# FPGA_Bank0-2.net
KiCad netlist of a schematic drawn in Altium Designer
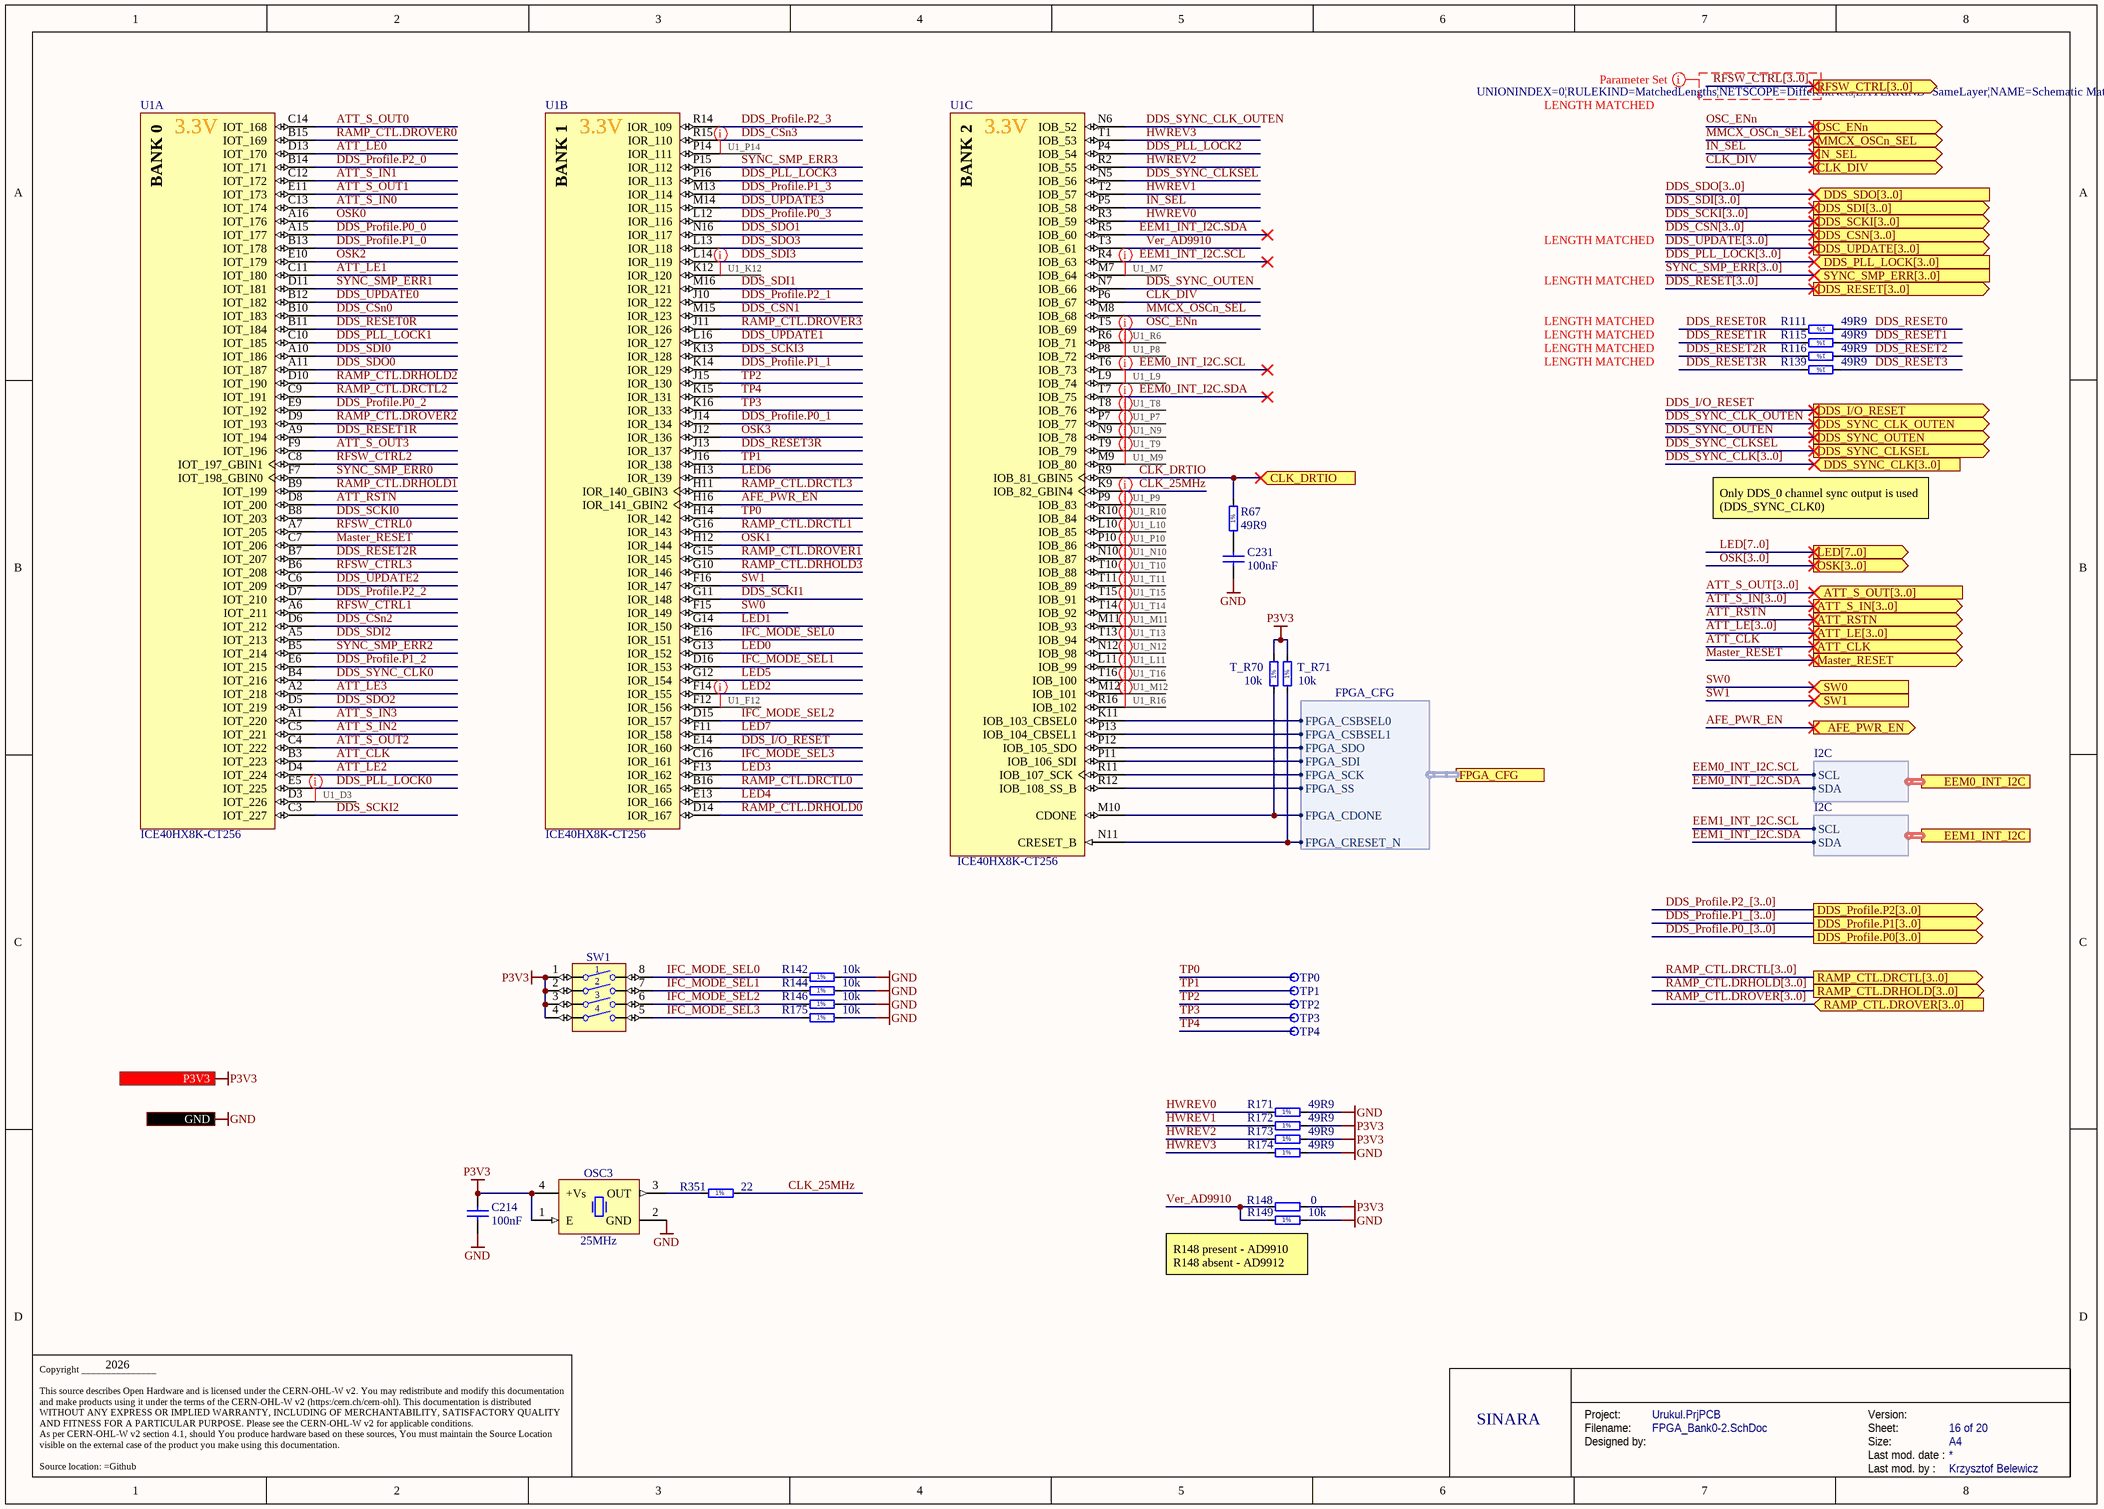
[diagram p0: FPGA_Bank0-2.SchDoc]

(export (version "E")
  (design (tool "Eeschema 10.0.6"))
  (components
    (comp (ref "C214")
      (value "100nF")
      (footprint "CAPC1005X55N")
      (description "Non-polarised capacitor")
      (fields
        (field (name "PART NUMBER") "CC0402_100NF_16V_10%_X5R")
        (field (name "VOLTAGE") "16V")
        (field (name "AUTHOR") "CERN DEM JLC")
      )
      (libsource (lib "Capacitors") (part "Capacitor - non polarized"))
    )
    (comp (ref "C231")
      (value "100nF")
      (footprint "CAPC1005X55N")
      (description "Non-polarised capacitor")
      (fields
        (field (name "PART NUMBER") "CC0402_100NF_16V_10%_X5R")
        (field (name "VOLTAGE") "16V")
        (field (name "AUTHOR") "CERN DEM JLC")
      )
      (libsource (lib "Capacitors") (part "Capacitor - non polarized"))
    )
    (comp (ref "OSC3")
      (value "25MHz")
      (footprint "OSC_IQD_CFPS-39")
      (description "Oscillator 4 pins 1=E 2=GND 3=OUT 4=+Vs")
      (fields
        (field (name "PART NUMBER") "OSC_25MHZ_IQD_LFSPXO025165")
        (field (name "MANUFACTURER") "IQD FREQUENCY PRODUCTS")
        (field (name "AUTHOR") "CERN DEM JLC")
      )
      (libsource (lib "ICs And Semiconductors") (part "Oscillator 1E 2GND 3OUT 4Vs"))
    )
    (comp (ref "R67")
      (value "49R9")
      (footprint "RESC1005X40N")
      (description "Resistor - 1%")
      (fields
        (field (name "PART NUMBER") "R0402_49R9_1%_0.0625W_100PPM")
        (field (name "POWER") "0.0625W")
        (field (name "AUTHOR") "CERN DEM JLC")
      )
      (libsource (lib "Resistors") (part "Resistor - 1%"))
    )
    (comp (ref "R111")
      (value "49R9")
      (footprint "RESC1005X40N")
      (description "Resistor - 1%")
      (fields
        (field (name "PART NUMBER") "R0402_49R9_1%_0.0625W_100PPM")
        (field (name "POWER") "0.0625W")
        (field (name "AUTHOR") "CERN DEM JLC")
      )
      (libsource (lib "Resistors") (part "Resistor - 1%"))
    )
    (comp (ref "R115")
      (value "49R9")
      (footprint "RESC1005X40N")
      (description "Resistor - 1%")
      (fields
        (field (name "PART NUMBER") "R0402_49R9_1%_0.0625W_100PPM")
        (field (name "POWER") "0.0625W")
        (field (name "AUTHOR") "CERN DEM JLC")
      )
      (libsource (lib "Resistors") (part "Resistor - 1%"))
    )
    (comp (ref "R116")
      (value "49R9")
      (footprint "RESC1005X40N")
      (description "Resistor - 1%")
      (fields
        (field (name "PART NUMBER") "R0402_49R9_1%_0.0625W_100PPM")
        (field (name "POWER") "0.0625W")
        (field (name "AUTHOR") "CERN DEM JLC")
      )
      (libsource (lib "Resistors") (part "Resistor - 1%"))
    )
    (comp (ref "R139")
      (value "49R9")
      (footprint "RESC1005X40N")
      (description "Resistor - 1%")
      (fields
        (field (name "PART NUMBER") "R0402_49R9_1%_0.0625W_100PPM")
        (field (name "POWER") "0.0625W")
        (field (name "AUTHOR") "CERN DEM JLC")
      )
      (libsource (lib "Resistors") (part "Resistor - 1%"))
    )
    (comp (ref "R142")
      (value "10k")
      (footprint "RESC1005X40N")
      (description "Resistor - 1%")
      (fields
        (field (name "PART NUMBER") "R0402_10K_1%_0.0625W_100PPM")
        (field (name "POWER") "0.0625W")
        (field (name "AUTHOR") "CERN DEM JLC")
      )
      (libsource (lib "Resistors") (part "Resistor - 1%"))
    )
    (comp (ref "R144")
      (value "10k")
      (footprint "RESC1005X40N")
      (description "Resistor - 1%")
      (fields
        (field (name "PART NUMBER") "R0402_10K_1%_0.0625W_100PPM")
        (field (name "POWER") "0.0625W")
        (field (name "AUTHOR") "CERN DEM JLC")
      )
      (libsource (lib "Resistors") (part "Resistor - 1%"))
    )
    (comp (ref "R146")
      (value "10k")
      (footprint "RESC1005X40N")
      (description "Resistor - 1%")
      (fields
        (field (name "PART NUMBER") "R0402_10K_1%_0.0625W_100PPM")
        (field (name "POWER") "0.0625W")
        (field (name "AUTHOR") "CERN DEM JLC")
      )
      (libsource (lib "Resistors") (part "Resistor - 1%"))
    )
    (comp (ref "R148")
      (value "0")
      (footprint "RESC1005X40N")
      (description "Resistor")
      (fields
        (field (name "PART NUMBER") "R0402_0R_JUMPER")
        (field (name "MANUFACTURER") "GENERIC")
        (field (name "AUTHOR") "CERN DEM JLC")
      )
      (libsource (lib "Resistors") (part "Resistor"))
    )
    (comp (ref "R149")
      (value "10k")
      (footprint "RESC1005X40N")
      (description "Resistor - 1%")
      (fields
        (field (name "PART NUMBER") "R0402_10K_1%_0.0625W_100PPM")
        (field (name "POWER") "0.0625W")
        (field (name "AUTHOR") "CERN DEM JLC")
      )
      (libsource (lib "Resistors") (part "Resistor - 1%"))
    )
    (comp (ref "R171")
      (value "49R9")
      (footprint "RESC1005X40N")
      (description "Resistor - 1%")
      (fields
        (field (name "PART NUMBER") "R0402_49R9_1%_0.0625W_100PPM")
        (field (name "POWER") "0.0625W")
        (field (name "AUTHOR") "CERN DEM JLC")
      )
      (libsource (lib "Resistors") (part "Resistor - 1%"))
    )
    (comp (ref "R172")
      (value "49R9")
      (footprint "RESC1005X40N")
      (description "Resistor - 1%")
      (fields
        (field (name "PART NUMBER") "R0402_49R9_1%_0.0625W_100PPM")
        (field (name "POWER") "0.0625W")
        (field (name "AUTHOR") "CERN DEM JLC")
      )
      (libsource (lib "Resistors") (part "Resistor - 1%"))
    )
    (comp (ref "R173")
      (value "49R9")
      (footprint "RESC1005X40N")
      (description "Resistor - 1%")
      (fields
        (field (name "PART NUMBER") "R0402_49R9_1%_0.0625W_100PPM")
        (field (name "POWER") "0.0625W")
        (field (name "AUTHOR") "CERN DEM JLC")
      )
      (libsource (lib "Resistors") (part "Resistor - 1%"))
    )
    (comp (ref "R174")
      (value "49R9")
      (footprint "RESC1005X40N")
      (description "Resistor - 1%")
      (fields
        (field (name "PART NUMBER") "R0402_49R9_1%_0.0625W_100PPM")
        (field (name "POWER") "0.0625W")
        (field (name "AUTHOR") "CERN DEM JLC")
      )
      (libsource (lib "Resistors") (part "Resistor - 1%"))
    )
    (comp (ref "R175")
      (value "10k")
      (footprint "RESC1005X40N")
      (description "Resistor - 1%")
      (fields
        (field (name "PART NUMBER") "R0402_10K_1%_0.0625W_100PPM")
        (field (name "POWER") "0.0625W")
        (field (name "AUTHOR") "CERN DEM JLC")
      )
      (libsource (lib "Resistors") (part "Resistor - 1%"))
    )
    (comp (ref "R351")
      (value "22")
      (footprint "RESC1005X40N")
      (description "Resistor - 1%")
      (fields
        (field (name "PART NUMBER") "R0402_22R_1%_0.0625W_100PPM")
        (field (name "POWER") "0.0625W")
        (field (name "AUTHOR") "CERN DEM JLC")
      )
      (libsource (lib "Resistors") (part "Resistor - 1%"))
    )
    (comp (ref "SW1")
      (value "Switch")
      (footprint "SW_TYCO_1571983-4")
      (description "4 Ways SPST DIP Switch")
      (fields
        (field (name "PART NUMBER") "SW_TYCO_1571983-4")
        (field (name "MANUFACTURER") "TYCO")
        (field (name "AUTHOR") "CERN DEM JLC")
      )
      (libsource (lib "Eletro-mechanical") (part "SW 4x SPST DIP Switch"))
    )
    (comp (ref "TP0")
      (value "Test Point")
      (footprint "TPS127")
      (fields (field (name "PART NUMBER") "SMD_PAD_1.27X1.27MM") (field (name "AUTHOR") "CERN DEM JLC"))
      (libsource (lib "Eletro-mechanical") (part "Test Point"))
    )
    (comp (ref "TP1")
      (value "Test Point")
      (footprint "TPS127")
      (fields (field (name "PART NUMBER") "SMD_PAD_1.27X1.27MM") (field (name "AUTHOR") "CERN DEM JLC"))
      (libsource (lib "Eletro-mechanical") (part "Test Point"))
    )
    (comp (ref "TP2")
      (value "Test Point")
      (footprint "TPS127")
      (fields (field (name "PART NUMBER") "SMD_PAD_1.27X1.27MM") (field (name "AUTHOR") "CERN DEM JLC"))
      (libsource (lib "Eletro-mechanical") (part "Test Point"))
    )
    (comp (ref "TP3")
      (value "Test Point")
      (footprint "TPS127")
      (fields (field (name "PART NUMBER") "SMD_PAD_1.27X1.27MM") (field (name "AUTHOR") "CERN DEM JLC"))
      (libsource (lib "Eletro-mechanical") (part "Test Point"))
    )
    (comp (ref "TP4")
      (value "Test Point")
      (footprint "TPS127")
      (fields (field (name "PART NUMBER") "SMD_PAD_1.27X1.27MM") (field (name "AUTHOR") "CERN DEM JLC"))
      (libsource (lib "Eletro-mechanical") (part "Test Point"))
    )
    (comp (ref "T_R70")
      (value "10k")
      (footprint "RESC1005X40N")
      (description "Resistor - 1%")
      (fields
        (field (name "PART NUMBER") "R0402_10K_1%_0.0625W_100PPM")
        (field (name "POWER") "0.0625W")
        (field (name "AUTHOR") "CERN DEM JLC")
      )
      (libsource (lib "Resistors") (part "Resistor - 1%"))
    )
    (comp (ref "T_R71")
      (value "10k")
      (footprint "RESC1005X40N")
      (description "Resistor - 1%")
      (fields
        (field (name "PART NUMBER") "R0402_10K_1%_0.0625W_100PPM")
        (field (name "POWER") "0.0625W")
        (field (name "AUTHOR") "CERN DEM JLC")
      )
      (libsource (lib "Resistors") (part "Resistor - 1%"))
    )
    (comp (ref "U1")
      (value "ICE40HX8K-CT256")
      (footprint "LATC-caBGA-256")
      (fields (field (name "MANUFACTURER") "Lattice Semiconductor"))
      (libsource (lib "Altium Content Vault") (part "LATC-HX8K-caBGA-256"))
    )
  )
  (nets
    (net (code "9") (name "/AFE_PWR_EN") (class "Default")
      (node (ref "U1") (pin "H16") (pinfunction "IOR_141_GBIN2_H16") (pintype "bidirectional+no_connect"))
    )
    (net (code "10") (name "/ATT_CLK") (class "Default")
      (node (ref "U1") (pin "B3") (pinfunction "IOT_223_B3") (pintype "bidirectional+no_connect"))
    )
    (net (code "11") (name "/ATT_LE0") (class "Default")
      (node (ref "U1") (pin "D13") (pinfunction "IOT_170_D13") (pintype "bidirectional"))
    )
    (net (code "12") (name "/ATT_LE1") (class "Default")
      (node (ref "U1") (pin "C11") (pinfunction "IOT_180_C11") (pintype "bidirectional"))
    )
    (net (code "13") (name "/ATT_LE2") (class "Default")
      (node (ref "U1") (pin "D4") (pinfunction "IOT_224_D4") (pintype "bidirectional"))
    )
    (net (code "14") (name "/ATT_LE3") (class "Default")
      (node (ref "U1") (pin "A2") (pinfunction "IOT_218_A2") (pintype "bidirectional"))
    )
    (net (code "16") (name "/ATT_RSTN") (class "Default")
      (node (ref "U1") (pin "D8") (pinfunction "IOT_200_D8") (pintype "bidirectional+no_connect"))
    )
    (net (code "17") (name "/ATT_S_IN0") (class "Default")
      (node (ref "U1") (pin "C13") (pinfunction "IOT_174_C13") (pintype "bidirectional"))
    )
    (net (code "18") (name "/ATT_S_IN1") (class "Default")
      (node (ref "U1") (pin "C12") (pinfunction "IOT_172_C12") (pintype "bidirectional"))
    )
    (net (code "19") (name "/ATT_S_IN2") (class "Default")
      (node (ref "U1") (pin "C5") (pinfunction "IOT_221_C5") (pintype "bidirectional"))
    )
    (net (code "20") (name "/ATT_S_IN3") (class "Default")
      (node (ref "U1") (pin "A1") (pinfunction "IOT_220_A1") (pintype "bidirectional"))
    )
    (net (code "22") (name "/ATT_S_OUT0") (class "Default")
      (node (ref "U1") (pin "C14") (pinfunction "IOT_168_C14") (pintype "bidirectional"))
    )
    (net (code "23") (name "/ATT_S_OUT1") (class "Default")
      (node (ref "U1") (pin "E11") (pinfunction "IOT_173_E11") (pintype "bidirectional"))
    )
    (net (code "24") (name "/ATT_S_OUT2") (class "Default")
      (node (ref "U1") (pin "C4") (pinfunction "IOT_222_C4") (pintype "bidirectional"))
    )
    (net (code "25") (name "/ATT_S_OUT3") (class "Default")
      (node (ref "U1") (pin "F9") (pinfunction "IOT_196_F9") (pintype "bidirectional"))
    )
    (net (code "27") (name "/CLK_25MHz") (class "Default")
      (node (ref "R351") (pin "2") (pinfunction "2_2") (pintype "passive"))
      (node (ref "U1") (pin "K9") (pinfunction "IOB_82_GBIN4_K9") (pintype "bidirectional"))
    )
    (net (code "28") (name "/CLK_DIV") (class "Default")
      (node (ref "U1") (pin "P6") (pinfunction "IOB_67_P6") (pintype "bidirectional"))
    )
    (net (code "29") (name "/CLK_DRTIO") (class "Default")
      (node (ref "R67") (pin "2") (pinfunction "2_2") (pintype "passive"))
      (node (ref "U1") (pin "R9") (pinfunction "IOB_81_GBIN5_R9") (pintype "bidirectional"))
    )
    (net (code "30") (name "/DDS_CSN1") (class "Default")
      (node (ref "U1") (pin "M15") (pinfunction "IOR_123_M15") (pintype "bidirectional"))
    )
    (net (code "32") (name "/DDS_CSn0") (class "Default")
      (node (ref "U1") (pin "B10") (pinfunction "IOT_183_B10") (pintype "bidirectional"))
    )
    (net (code "33") (name "/DDS_CSn2") (class "Default")
      (node (ref "U1") (pin "D6") (pinfunction "IOT_212_D6") (pintype "bidirectional"))
    )
    (net (code "34") (name "/DDS_CSn3") (class "Default")
      (node (ref "U1") (pin "R15") (pinfunction "IOR_110_R15") (pintype "bidirectional"))
    )
    (net (code "35") (name "/DDS_I{slash}O_RESET") (class "Default")
      (node (ref "U1") (pin "E14") (pinfunction "IOR_160_E14") (pintype "bidirectional"))
    )
    (net (code "36") (name "/DDS_PLL_LOCK0") (class "Default")
      (node (ref "U1") (pin "E5") (pinfunction "IOT_225_E5") (pintype "bidirectional"))
    )
    (net (code "37") (name "/DDS_PLL_LOCK1") (class "Default")
      (node (ref "U1") (pin "C10") (pinfunction "IOT_185_C10") (pintype "bidirectional"))
    )
    (net (code "38") (name "/DDS_PLL_LOCK2") (class "Default")
      (node (ref "U1") (pin "P4") (pinfunction "IOB_54_P4") (pintype "bidirectional"))
    )
    (net (code "39") (name "/DDS_PLL_LOCK3") (class "Default")
      (node (ref "U1") (pin "P16") (pinfunction "IOR_113_P16") (pintype "bidirectional"))
    )
    (net (code "41") (name "/DDS_Profile.P0_0") (class "Default")
      (node (ref "U1") (pin "A15") (pinfunction "IOT_177_A15") (pintype "bidirectional"))
    )
    (net (code "42") (name "/DDS_Profile.P0_1") (class "Default")
      (node (ref "U1") (pin "J14") (pinfunction "IOR_134_J14") (pintype "bidirectional"))
    )
    (net (code "43") (name "/DDS_Profile.P0_2") (class "Default")
      (node (ref "U1") (pin "E9") (pinfunction "IOT_192_E9") (pintype "bidirectional"))
    )
    (net (code "44") (name "/DDS_Profile.P0_3") (class "Default")
      (node (ref "U1") (pin "L12") (pinfunction "IOR_116_L12") (pintype "bidirectional"))
    )
    (net (code "46") (name "/DDS_Profile.P1_0") (class "Default")
      (node (ref "U1") (pin "B13") (pinfunction "IOT_178_B13") (pintype "bidirectional"))
    )
    (net (code "47") (name "/DDS_Profile.P1_1") (class "Default")
      (node (ref "U1") (pin "K14") (pinfunction "IOR_129_K14") (pintype "bidirectional"))
    )
    (net (code "48") (name "/DDS_Profile.P1_2") (class "Default")
      (node (ref "U1") (pin "E6") (pinfunction "IOT_215_E6") (pintype "bidirectional"))
    )
    (net (code "49") (name "/DDS_Profile.P1_3") (class "Default")
      (node (ref "U1") (pin "M13") (pinfunction "IOR_114_M13") (pintype "bidirectional"))
    )
    (net (code "51") (name "/DDS_Profile.P2_0") (class "Default")
      (node (ref "U1") (pin "B14") (pinfunction "IOT_171_B14") (pintype "bidirectional"))
    )
    (net (code "52") (name "/DDS_Profile.P2_1") (class "Default")
      (node (ref "U1") (pin "J10") (pinfunction "IOR_122_J10") (pintype "bidirectional"))
    )
    (net (code "53") (name "/DDS_Profile.P2_2") (class "Default")
      (node (ref "U1") (pin "D7") (pinfunction "IOT_210_D7") (pintype "bidirectional"))
    )
    (net (code "54") (name "/DDS_Profile.P2_3") (class "Default")
      (node (ref "U1") (pin "R14") (pinfunction "IOR_109_R14") (pintype "bidirectional"))
    )
    (net (code "56") (name "/DDS_RESET0") (class "Default")
      (node (ref "R111") (pin "1") (pinfunction "1_1") (pintype "passive"))
    )
    (net (code "57") (name "/DDS_RESET0R") (class "Default")
      (node (ref "R111") (pin "2") (pinfunction "2_2") (pintype "passive"))
      (node (ref "U1") (pin "B11") (pinfunction "IOT_184_B11") (pintype "bidirectional"))
    )
    (net (code "58") (name "/DDS_RESET1") (class "Default")
      (node (ref "R115") (pin "1") (pinfunction "1_1") (pintype "passive"))
    )
    (net (code "59") (name "/DDS_RESET1R") (class "Default")
      (node (ref "R115") (pin "2") (pinfunction "2_2") (pintype "passive"))
      (node (ref "U1") (pin "A9") (pinfunction "IOT_194_A9") (pintype "bidirectional"))
    )
    (net (code "60") (name "/DDS_RESET2") (class "Default")
      (node (ref "R116") (pin "1") (pinfunction "1_1") (pintype "passive"))
    )
    (net (code "61") (name "/DDS_RESET2R") (class "Default")
      (node (ref "R116") (pin "2") (pinfunction "2_2") (pintype "passive"))
      (node (ref "U1") (pin "B7") (pinfunction "IOT_207_B7") (pintype "bidirectional"))
    )
    (net (code "62") (name "/DDS_RESET3") (class "Default")
      (node (ref "R139") (pin "1") (pinfunction "1_1") (pintype "passive"))
    )
    (net (code "63") (name "/DDS_RESET3R") (class "Default")
      (node (ref "R139") (pin "2") (pinfunction "2_2") (pintype "passive"))
      (node (ref "U1") (pin "J13") (pinfunction "IOR_137_J13") (pintype "bidirectional"))
    )
    (net (code "65") (name "/DDS_SCKI0") (class "Default")
      (node (ref "U1") (pin "B8") (pinfunction "IOT_203_B8") (pintype "bidirectional"))
    )
    (net (code "66") (name "/DDS_SCKI1") (class "Default")
      (node (ref "U1") (pin "G11") (pinfunction "IOR_148_G11") (pintype "bidirectional"))
    )
    (net (code "67") (name "/DDS_SCKI2") (class "Default")
      (node (ref "U1") (pin "C3") (pinfunction "IOT_227_C3") (pintype "bidirectional"))
    )
    (net (code "68") (name "/DDS_SCKI3") (class "Default")
      (node (ref "U1") (pin "K13") (pinfunction "IOR_128_K13") (pintype "bidirectional"))
    )
    (net (code "70") (name "/DDS_SDI0") (class "Default")
      (node (ref "U1") (pin "A10") (pinfunction "IOT_186_A10") (pintype "bidirectional"))
    )
    (net (code "71") (name "/DDS_SDI1") (class "Default")
      (node (ref "U1") (pin "M16") (pinfunction "IOR_121_M16") (pintype "bidirectional"))
    )
    (net (code "72") (name "/DDS_SDI2") (class "Default")
      (node (ref "U1") (pin "A5") (pinfunction "IOT_213_A5") (pintype "bidirectional"))
    )
    (net (code "73") (name "/DDS_SDI3") (class "Default")
      (node (ref "U1") (pin "L14") (pinfunction "IOR_119_L14") (pintype "bidirectional"))
    )
    (net (code "75") (name "/DDS_SDO0") (class "Default")
      (node (ref "U1") (pin "A11") (pinfunction "IOT_187_A11") (pintype "bidirectional"))
    )
    (net (code "76") (name "/DDS_SDO1") (class "Default")
      (node (ref "U1") (pin "N16") (pinfunction "IOR_117_N16") (pintype "bidirectional"))
    )
    (net (code "77") (name "/DDS_SDO2") (class "Default")
      (node (ref "U1") (pin "D5") (pinfunction "IOT_219_D5") (pintype "bidirectional"))
    )
    (net (code "78") (name "/DDS_SDO3") (class "Default")
      (node (ref "U1") (pin "L13") (pinfunction "IOR_118_L13") (pintype "bidirectional"))
    )
    (net (code "80") (name "/DDS_SYNC_CLK0") (class "Default")
      (node (ref "U1") (pin "B4") (pinfunction "IOT_216_B4") (pintype "bidirectional"))
    )
    (net (code "81") (name "/DDS_SYNC_CLKSEL") (class "Default")
      (node (ref "U1") (pin "N5") (pinfunction "IOB_56_N5") (pintype "bidirectional"))
    )
    (net (code "83") (name "/DDS_SYNC_CLK_OUTEN") (class "Default")
      (node (ref "U1") (pin "N6") (pinfunction "IOB_52_N6") (pintype "bidirectional"))
    )
    (net (code "84") (name "/DDS_SYNC_OUTEN") (class "Default")
      (node (ref "U1") (pin "N7") (pinfunction "IOB_66_N7") (pintype "bidirectional"))
    )
    (net (code "85") (name "/DDS_UPDATE0") (class "Default")
      (node (ref "U1") (pin "B12") (pinfunction "IOT_182_B12") (pintype "bidirectional"))
    )
    (net (code "86") (name "/DDS_UPDATE1") (class "Default")
      (node (ref "U1") (pin "L16") (pinfunction "IOR_127_L16") (pintype "bidirectional"))
    )
    (net (code "87") (name "/DDS_UPDATE2") (class "Default")
      (node (ref "U1") (pin "C6") (pinfunction "IOT_209_C6") (pintype "bidirectional"))
    )
    (net (code "88") (name "/DDS_UPDATE3") (class "Default")
      (node (ref "U1") (pin "M14") (pinfunction "IOR_115_M14") (pintype "bidirectional"))
    )
    (net (code "90") (name "/EEM0_INT_I2C.SCL") (class "Default")
      (node (ref "U1") (pin "T6") (pinfunction "IOB_73_T6") (pintype "bidirectional"))
    )
    (net (code "91") (name "/EEM0_INT_I2C.SDA") (class "Default")
      (node (ref "U1") (pin "T7") (pinfunction "IOB_75_T7") (pintype "bidirectional"))
    )
    (net (code "92") (name "/EEM1_INT_I2C.SCL") (class "Default")
      (node (ref "U1") (pin "R4") (pinfunction "IOB_63_R4") (pintype "bidirectional"))
    )
    (net (code "93") (name "/EEM1_INT_I2C.SDA") (class "Default")
      (node (ref "U1") (pin "R5") (pinfunction "IOB_60_R5") (pintype "bidirectional"))
    )
    (net (code "94") (name "/FPGA_CDONE") (class "Default")
      (node (ref "T_R70") (pin "1") (pinfunction "1_1") (pintype "passive"))
      (node (ref "U1") (pin "M10") (pinfunction "CDONE_M10") (pintype "bidirectional"))
    )
    (net (code "95") (name "/FPGA_CRESET_N") (class "Default")
      (node (ref "T_R71") (pin "1") (pinfunction "1_1") (pintype "passive"))
      (node (ref "U1") (pin "N11") (pinfunction "CRESET_B_N11") (pintype "input"))
    )
    (net (code "96") (name "/FPGA_CSBSEL0") (class "Default")
      (node (ref "U1") (pin "K11") (pinfunction "IOB_103_CBSEL0_K11") (pintype "bidirectional"))
    )
    (net (code "97") (name "/FPGA_CSBSEL1") (class "Default")
      (node (ref "U1") (pin "P13") (pinfunction "IOB_104_CBSEL1_P13") (pintype "bidirectional"))
    )
    (net (code "98") (name "/FPGA_SCK") (class "Default")
      (node (ref "U1") (pin "R11") (pinfunction "IOB_107_SCK_R11") (pintype "bidirectional"))
    )
    (net (code "99") (name "/FPGA_SDI") (class "Default")
      (node (ref "U1") (pin "P11") (pinfunction "IOB_106_SDI_P11") (pintype "bidirectional"))
    )
    (net (code "100") (name "/FPGA_SDO") (class "Default")
      (node (ref "U1") (pin "P12") (pinfunction "IOB_105_SDO_P12") (pintype "bidirectional"))
    )
    (net (code "101") (name "/FPGA_SS") (class "Default")
      (node (ref "U1") (pin "R12") (pinfunction "IOB_108_SS_B_R12") (pintype "bidirectional"))
    )
    (net (code "102") (name "/HWREV0") (class "Default")
      (node (ref "R171") (pin "2") (pinfunction "2_2") (pintype "passive"))
      (node (ref "U1") (pin "R3") (pinfunction "IOB_59_R3") (pintype "bidirectional"))
    )
    (net (code "103") (name "/HWREV1") (class "Default")
      (node (ref "R172") (pin "2") (pinfunction "2_2") (pintype "passive"))
      (node (ref "U1") (pin "T2") (pinfunction "IOB_57_T2") (pintype "bidirectional"))
    )
    (net (code "104") (name "/HWREV2") (class "Default")
      (node (ref "R173") (pin "2") (pinfunction "2_2") (pintype "passive"))
      (node (ref "U1") (pin "R2") (pinfunction "IOB_55_R2") (pintype "bidirectional"))
    )
    (net (code "105") (name "/HWREV3") (class "Default")
      (node (ref "R174") (pin "2") (pinfunction "2_2") (pintype "passive"))
      (node (ref "U1") (pin "T1") (pinfunction "IOB_53_T1") (pintype "bidirectional"))
    )
    (net (code "106") (name "/IFC_MODE_SEL0") (class "Default")
      (node (ref "R142") (pin "2") (pinfunction "2_2") (pintype "passive"))
      (node (ref "SW1") (pin "8") (pinfunction "8_8") (pintype "bidirectional"))
      (node (ref "U1") (pin "E16") (pinfunction "IOR_151_E16") (pintype "bidirectional"))
    )
    (net (code "107") (name "/IFC_MODE_SEL1") (class "Default")
      (node (ref "R144") (pin "2") (pinfunction "2_2") (pintype "passive"))
      (node (ref "SW1") (pin "7") (pinfunction "7_7") (pintype "bidirectional"))
      (node (ref "U1") (pin "D16") (pinfunction "IOR_153_D16") (pintype "bidirectional"))
    )
    (net (code "108") (name "/IFC_MODE_SEL2") (class "Default")
      (node (ref "R146") (pin "2") (pinfunction "2_2") (pintype "passive"))
      (node (ref "SW1") (pin "6") (pinfunction "6_6") (pintype "bidirectional"))
      (node (ref "U1") (pin "D15") (pinfunction "IOR_157_D15") (pintype "bidirectional"))
    )
    (net (code "109") (name "/IFC_MODE_SEL3") (class "Default")
      (node (ref "R175") (pin "2") (pinfunction "2_2") (pintype "passive"))
      (node (ref "SW1") (pin "5") (pinfunction "5_5") (pintype "bidirectional"))
      (node (ref "U1") (pin "C16") (pinfunction "IOR_161_C16") (pintype "bidirectional"))
    )
    (net (code "110") (name "/IN_SEL") (class "Default")
      (node (ref "U1") (pin "P5") (pinfunction "IOB_58_P5") (pintype "bidirectional"))
    )
    (net (code "111") (name "/LED0") (class "Default")
      (node (ref "U1") (pin "G13") (pinfunction "IOR_152_G13") (pintype "bidirectional"))
    )
    (net (code "112") (name "/LED1") (class "Default")
      (node (ref "U1") (pin "G14") (pinfunction "IOR_150_G14") (pintype "bidirectional"))
    )
    (net (code "113") (name "/LED2") (class "Default")
      (node (ref "U1") (pin "F14") (pinfunction "IOR_155_F14") (pintype "bidirectional"))
    )
    (net (code "114") (name "/LED3") (class "Default")
      (node (ref "U1") (pin "F13") (pinfunction "IOR_162_F13") (pintype "bidirectional"))
    )
    (net (code "115") (name "/LED4") (class "Default")
      (node (ref "U1") (pin "E13") (pinfunction "IOR_166_E13") (pintype "bidirectional"))
    )
    (net (code "116") (name "/LED5") (class "Default")
      (node (ref "U1") (pin "G12") (pinfunction "IOR_154_G12") (pintype "bidirectional"))
    )
    (net (code "117") (name "/LED6") (class "Default")
      (node (ref "U1") (pin "H13") (pinfunction "IOR_139_H13") (pintype "bidirectional"))
    )
    (net (code "118") (name "/LED7") (class "Default")
      (node (ref "U1") (pin "F11") (pinfunction "IOR_158_F11") (pintype "bidirectional"))
    )
    (net (code "120") (name "/MMCX_OSCn_SEL") (class "Default")
      (node (ref "U1") (pin "M8") (pinfunction "IOB_68_M8") (pintype "bidirectional"))
    )
    (net (code "121") (name "/Master_RESET") (class "Default")
      (node (ref "U1") (pin "C7") (pinfunction "IOT_206_C7") (pintype "bidirectional+no_connect"))
    )
    (net (code "122") (name "/OSC_ENn") (class "Default")
      (node (ref "U1") (pin "T5") (pinfunction "IOB_69_T5") (pintype "bidirectional"))
    )
    (net (code "123") (name "/OSK0") (class "Default")
      (node (ref "U1") (pin "A16") (pinfunction "IOT_176_A16") (pintype "bidirectional"))
    )
    (net (code "124") (name "/OSK1") (class "Default")
      (node (ref "U1") (pin "H12") (pinfunction "IOR_144_H12") (pintype "bidirectional"))
    )
    (net (code "125") (name "/OSK2") (class "Default")
      (node (ref "U1") (pin "E10") (pinfunction "IOT_179_E10") (pintype "bidirectional"))
    )
    (net (code "126") (name "/OSK3") (class "Default")
      (node (ref "U1") (pin "J12") (pinfunction "IOR_136_J12") (pintype "bidirectional"))
    )
    (net (code "128") (name "/RAMP_CTL.DRCTL0") (class "Default")
      (node (ref "U1") (pin "B16") (pinfunction "IOR_165_B16") (pintype "bidirectional"))
    )
    (net (code "129") (name "/RAMP_CTL.DRCTL1") (class "Default")
      (node (ref "U1") (pin "G16") (pinfunction "IOR_143_G16") (pintype "bidirectional"))
    )
    (net (code "130") (name "/RAMP_CTL.DRCTL2") (class "Default")
      (node (ref "U1") (pin "C9") (pinfunction "IOT_191_C9") (pintype "bidirectional"))
    )
    (net (code "131") (name "/RAMP_CTL.DRCTL3") (class "Default")
      (node (ref "U1") (pin "H11") (pinfunction "IOR_140_GBIN3_H11") (pintype "bidirectional"))
    )
    (net (code "133") (name "/RAMP_CTL.DRHOLD0") (class "Default")
      (node (ref "U1") (pin "D14") (pinfunction "IOR_167_D14") (pintype "bidirectional"))
    )
    (net (code "134") (name "/RAMP_CTL.DRHOLD1") (class "Default")
      (node (ref "U1") (pin "B9") (pinfunction "IOT_199_B9") (pintype "bidirectional"))
    )
    (net (code "135") (name "/RAMP_CTL.DRHOLD2") (class "Default")
      (node (ref "U1") (pin "D10") (pinfunction "IOT_190_D10") (pintype "bidirectional"))
    )
    (net (code "136") (name "/RAMP_CTL.DRHOLD3") (class "Default")
      (node (ref "U1") (pin "G10") (pinfunction "IOR_146_G10") (pintype "bidirectional"))
    )
    (net (code "138") (name "/RAMP_CTL.DROVER0") (class "Default")
      (node (ref "U1") (pin "B15") (pinfunction "IOT_169_B15") (pintype "bidirectional"))
    )
    (net (code "139") (name "/RAMP_CTL.DROVER1") (class "Default")
      (node (ref "U1") (pin "G15") (pinfunction "IOR_145_G15") (pintype "bidirectional"))
    )
    (net (code "140") (name "/RAMP_CTL.DROVER2") (class "Default")
      (node (ref "U1") (pin "D9") (pinfunction "IOT_193_D9") (pintype "bidirectional"))
    )
    (net (code "141") (name "/RAMP_CTL.DROVER3") (class "Default")
      (node (ref "U1") (pin "J11") (pinfunction "IOR_126_J11") (pintype "bidirectional"))
    )
    (net (code "143") (name "/RFSW_CTRL0") (class "Default")
      (node (ref "U1") (pin "A7") (pinfunction "IOT_205_A7") (pintype "bidirectional"))
    )
    (net (code "144") (name "/RFSW_CTRL1") (class "Default")
      (node (ref "U1") (pin "A6") (pinfunction "IOT_211_A6") (pintype "bidirectional"))
    )
    (net (code "145") (name "/RFSW_CTRL2") (class "Default")
      (node (ref "U1") (pin "C8") (pinfunction "IOT_197_GBIN1_C8") (pintype "bidirectional"))
    )
    (net (code "146") (name "/RFSW_CTRL3") (class "Default")
      (node (ref "U1") (pin "B6") (pinfunction "IOT_208_B6") (pintype "bidirectional"))
    )
    (net (code "148") (name "/SW0") (class "Default")
      (node (ref "U1") (pin "F15") (pinfunction "IOR_149_F15") (pintype "bidirectional+no_connect"))
    )
    (net (code "149") (name "/SW1") (class "Default")
      (node (ref "U1") (pin "F16") (pinfunction "IOR_147_F16") (pintype "bidirectional+no_connect"))
    )
    (net (code "150") (name "/SYNC_SMP_ERR0") (class "Default")
      (node (ref "U1") (pin "F7") (pinfunction "IOT_198_GBIN0_F7") (pintype "bidirectional"))
    )
    (net (code "151") (name "/SYNC_SMP_ERR1") (class "Default")
      (node (ref "U1") (pin "D11") (pinfunction "IOT_181_D11") (pintype "bidirectional"))
    )
    (net (code "152") (name "/SYNC_SMP_ERR2") (class "Default")
      (node (ref "U1") (pin "B5") (pinfunction "IOT_214_B5") (pintype "bidirectional"))
    )
    (net (code "153") (name "/SYNC_SMP_ERR3") (class "Default")
      (node (ref "U1") (pin "P15") (pinfunction "IOR_112_P15") (pintype "bidirectional"))
    )
    (net (code "155") (name "/TP0") (class "Default")
      (node (ref "TP0") (pin "1") (pinfunction "1_1") (pintype "bidirectional"))
      (node (ref "U1") (pin "H14") (pinfunction "IOR_142_H14") (pintype "bidirectional"))
    )
    (net (code "156") (name "/TP1") (class "Default")
      (node (ref "TP1") (pin "1") (pinfunction "1_1") (pintype "bidirectional"))
      (node (ref "U1") (pin "J16") (pinfunction "IOR_138_J16") (pintype "bidirectional"))
    )
    (net (code "157") (name "/TP2") (class "Default")
      (node (ref "TP2") (pin "1") (pinfunction "1_1") (pintype "bidirectional"))
      (node (ref "U1") (pin "J15") (pinfunction "IOR_130_J15") (pintype "bidirectional"))
    )
    (net (code "158") (name "/TP3") (class "Default")
      (node (ref "TP3") (pin "1") (pinfunction "1_1") (pintype "bidirectional"))
      (node (ref "U1") (pin "K16") (pinfunction "IOR_133_K16") (pintype "bidirectional"))
    )
    (net (code "159") (name "/TP4") (class "Default")
      (node (ref "TP4") (pin "1") (pinfunction "1_1") (pintype "bidirectional"))
      (node (ref "U1") (pin "K15") (pinfunction "IOR_131_K15") (pintype "bidirectional"))
    )
    (net (code "160") (name "/U1_D3") (class "Default")
      (node (ref "U1") (pin "D3") (pinfunction "IOT_226_D3") (pintype "bidirectional"))
    )
    (net (code "161") (name "/U1_F12") (class "Default")
      (node (ref "U1") (pin "F12") (pinfunction "IOR_156_F12") (pintype "bidirectional"))
    )
    (net (code "162") (name "/U1_K12") (class "Default")
      (node (ref "U1") (pin "K12") (pinfunction "IOR_120_K12") (pintype "bidirectional"))
    )
    (net (code "163") (name "/U1_L9") (class "Default")
      (node (ref "U1") (pin "L9") (pinfunction "IOB_74_L9") (pintype "bidirectional"))
    )
    (net (code "164") (name "/U1_L10") (class "Default")
      (node (ref "U1") (pin "L10") (pinfunction "IOB_85_L10") (pintype "bidirectional"))
    )
    (net (code "165") (name "/U1_L11") (class "Default")
      (node (ref "U1") (pin "L11") (pinfunction "IOB_99_L11") (pintype "bidirectional"))
    )
    (net (code "166") (name "/U1_M7") (class "Default")
      (node (ref "U1") (pin "M7") (pinfunction "IOB_64_M7") (pintype "bidirectional"))
    )
    (net (code "167") (name "/U1_M9") (class "Default")
      (node (ref "U1") (pin "M9") (pinfunction "IOB_80_M9") (pintype "bidirectional"))
    )
    (net (code "168") (name "/U1_M11") (class "Default")
      (node (ref "U1") (pin "M11") (pinfunction "IOB_93_M11") (pintype "bidirectional"))
    )
    (net (code "169") (name "/U1_M12") (class "Default")
      (node (ref "U1") (pin "M12") (pinfunction "IOB_101_M12") (pintype "bidirectional"))
    )
    (net (code "170") (name "/U1_N9") (class "Default")
      (node (ref "U1") (pin "N9") (pinfunction "IOB_78_N9") (pintype "bidirectional"))
    )
    (net (code "171") (name "/U1_N10") (class "Default")
      (node (ref "U1") (pin "N10") (pinfunction "IOB_87_N10") (pintype "bidirectional"))
    )
    (net (code "172") (name "/U1_N12") (class "Default")
      (node (ref "U1") (pin "N12") (pinfunction "IOB_98_N12") (pintype "bidirectional"))
    )
    (net (code "173") (name "/U1_P7") (class "Default")
      (node (ref "U1") (pin "P7") (pinfunction "IOB_77_P7") (pintype "bidirectional"))
    )
    (net (code "174") (name "/U1_P8") (class "Default")
      (node (ref "U1") (pin "P8") (pinfunction "IOB_72_P8") (pintype "bidirectional"))
    )
    (net (code "175") (name "/U1_P9") (class "Default")
      (node (ref "U1") (pin "P9") (pinfunction "IOB_83_P9") (pintype "bidirectional"))
    )
    (net (code "176") (name "/U1_P10") (class "Default")
      (node (ref "U1") (pin "P10") (pinfunction "IOB_86_P10") (pintype "bidirectional"))
    )
    (net (code "177") (name "/U1_P14") (class "Default")
      (node (ref "U1") (pin "P14") (pinfunction "IOR_111_P14") (pintype "bidirectional"))
    )
    (net (code "178") (name "/U1_R6") (class "Default")
      (node (ref "U1") (pin "R6") (pinfunction "IOB_71_R6") (pintype "bidirectional"))
    )
    (net (code "179") (name "/U1_R10") (class "Default")
      (node (ref "U1") (pin "R10") (pinfunction "IOB_84_R10") (pintype "bidirectional"))
    )
    (net (code "180") (name "/U1_R16") (class "Default")
      (node (ref "U1") (pin "R16") (pinfunction "IOB_102_R16") (pintype "bidirectional"))
    )
    (net (code "181") (name "/U1_T8") (class "Default")
      (node (ref "U1") (pin "T8") (pinfunction "IOB_76_T8") (pintype "bidirectional"))
    )
    (net (code "182") (name "/U1_T9") (class "Default")
      (node (ref "U1") (pin "T9") (pinfunction "IOB_79_T9") (pintype "bidirectional"))
    )
    (net (code "183") (name "/U1_T10") (class "Default")
      (node (ref "U1") (pin "T10") (pinfunction "IOB_88_T10") (pintype "bidirectional"))
    )
    (net (code "184") (name "/U1_T11") (class "Default")
      (node (ref "U1") (pin "T11") (pinfunction "IOB_89_T11") (pintype "bidirectional"))
    )
    (net (code "185") (name "/U1_T13") (class "Default")
      (node (ref "U1") (pin "T13") (pinfunction "IOB_94_T13") (pintype "bidirectional"))
    )
    (net (code "186") (name "/U1_T14") (class "Default")
      (node (ref "U1") (pin "T14") (pinfunction "IOB_92_T14") (pintype "bidirectional"))
    )
    (net (code "187") (name "/U1_T15") (class "Default")
      (node (ref "U1") (pin "T15") (pinfunction "IOB_91_T15") (pintype "bidirectional"))
    )
    (net (code "188") (name "/U1_T16") (class "Default")
      (node (ref "U1") (pin "T16") (pinfunction "IOB_100_T16") (pintype "bidirectional"))
    )
    (net (code "189") (name "/Ver_AD9910") (class "Default")
      (node (ref "R148") (pin "1") (pinfunction "1_1") (pintype "passive"))
      (node (ref "R149") (pin "2") (pinfunction "2_2") (pintype "passive"))
      (node (ref "U1") (pin "T3") (pinfunction "IOB_61_T3") (pintype "bidirectional"))
    )
    (net (code "192") (name "GND") (class "Default")
      (node (ref "C214") (pin "1") (pinfunction "1_1") (pintype "passive"))
      (node (ref "C231") (pin "1") (pinfunction "1_1") (pintype "passive"))
      (node (ref "OSC3") (pin "2") (pinfunction "GND_2") (pintype "power_in"))
      (node (ref "R142") (pin "1") (pinfunction "1_1") (pintype "passive"))
      (node (ref "R144") (pin "1") (pinfunction "1_1") (pintype "passive"))
      (node (ref "R146") (pin "1") (pinfunction "1_1") (pintype "passive"))
      (node (ref "R149") (pin "1") (pinfunction "1_1") (pintype "passive"))
      (node (ref "R171") (pin "1") (pinfunction "1_1") (pintype "passive"))
      (node (ref "R174") (pin "1") (pinfunction "1_1") (pintype "passive"))
      (node (ref "R175") (pin "1") (pinfunction "1_1") (pintype "passive"))
    )
    (net (code "193") (name "Net-(C231-Pad2)") (class "Default")
      (node (ref "C231") (pin "2") (pinfunction "2_2") (pintype "passive"))
      (node (ref "R67") (pin "1") (pinfunction "1_1") (pintype "passive"))
    )
    (net (code "194") (name "Net-(OSC3-OUT)") (class "Default")
      (node (ref "OSC3") (pin "3") (pinfunction "OUT_3") (pintype "output"))
      (node (ref "R351") (pin "1") (pinfunction "1_1") (pintype "passive"))
    )
    (net (code "195") (name "P3V3") (class "Default")
      (node (ref "C214") (pin "2") (pinfunction "2_2") (pintype "passive"))
      (node (ref "OSC3") (pin "1") (pinfunction "E_1") (pintype "input"))
      (node (ref "OSC3") (pin "4") (pinfunction "+Vs_4") (pintype "power_in"))
      (node (ref "R148") (pin "2") (pinfunction "2_2") (pintype "passive"))
      (node (ref "R172") (pin "1") (pinfunction "1_1") (pintype "passive"))
      (node (ref "R173") (pin "1") (pinfunction "1_1") (pintype "passive"))
      (node (ref "SW1") (pin "1") (pinfunction "1_1") (pintype "bidirectional"))
      (node (ref "SW1") (pin "2") (pinfunction "2_2") (pintype "bidirectional"))
      (node (ref "SW1") (pin "3") (pinfunction "3_3") (pintype "bidirectional"))
      (node (ref "SW1") (pin "4") (pinfunction "4_4") (pintype "bidirectional"))
      (node (ref "T_R70") (pin "2") (pinfunction "2_2") (pintype "passive"))
      (node (ref "T_R71") (pin "2") (pinfunction "2_2") (pintype "passive"))
    )
  )
)
